# amp_lm4780.net
KiCad netlist of a schematic drawn in EAGLE
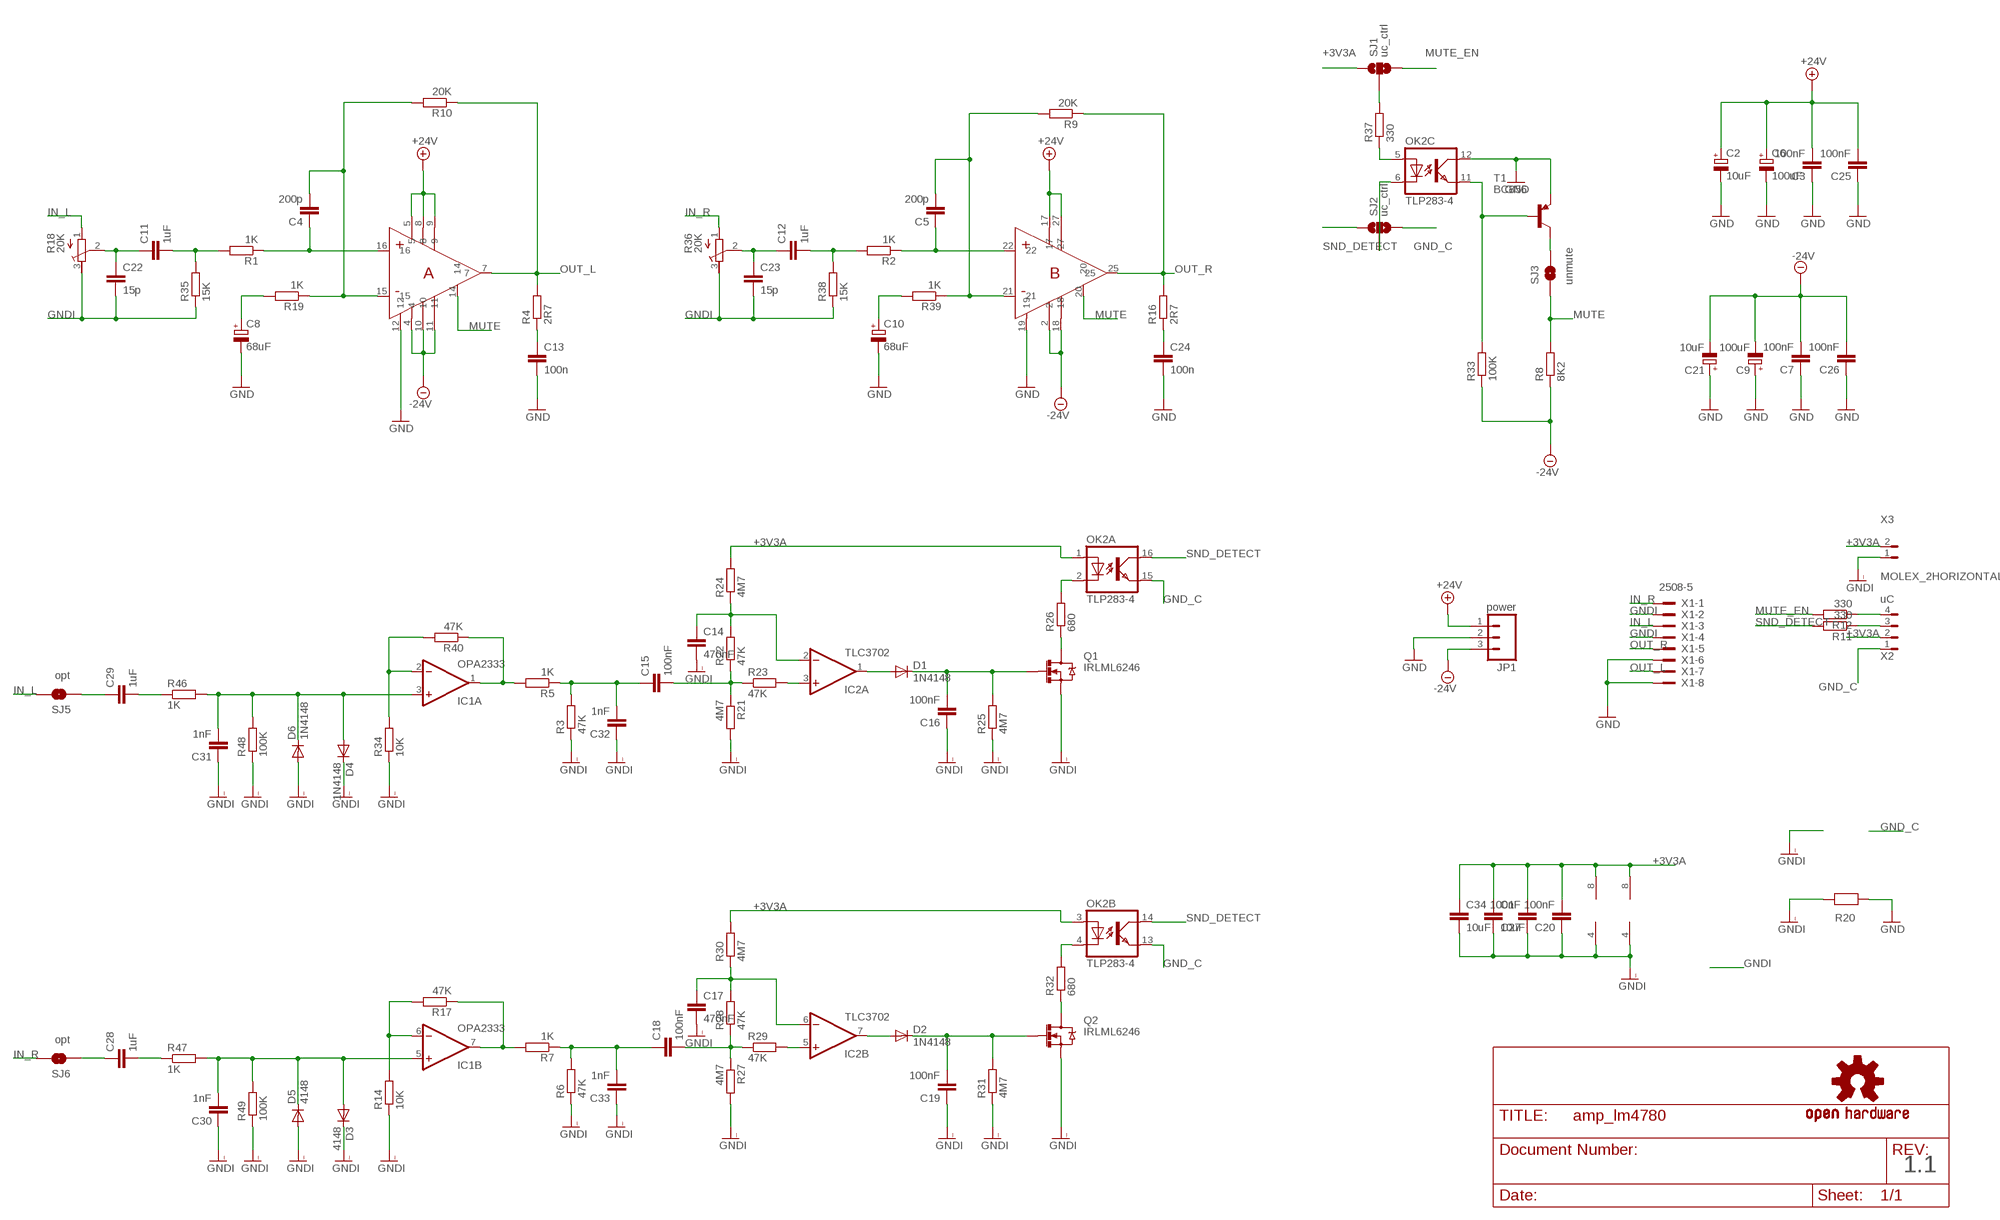
[diagram p0: schematic, sheet 1]

(export (version "E")
  (design (tool "Eeschema 10.0.6"))
  (components
    (comp (ref "C1")
      (value "10uF")
      (footprint "eagle-import:C1206K")
      (libsource (lib "eagle-import") (part "C-EUC1206K"))
    )
    (comp (ref "C2")
      (value "10uF")
      (footprint "eagle-import:PANASONIC_C")
      (libsource (lib "eagle-import") (part "CPOL-EUC"))
    )
    (comp (ref "C3")
      (value "100nF")
      (footprint "eagle-import:C0805")
      (libsource (lib "eagle-import") (part "C-EUC0805"))
    )
    (comp (ref "C4")
      (value "200p")
      (footprint "eagle-import:C0805")
      (libsource (lib "eagle-import") (part "C-EUC0805"))
    )
    (comp (ref "C5")
      (value "200p")
      (footprint "eagle-import:C0805")
      (libsource (lib "eagle-import") (part "C-EUC0805"))
    )
    (comp (ref "C6")
      (value "100uF")
      (footprint "eagle-import:PANASONIC_G")
      (libsource (lib "eagle-import") (part "CPOL-EUG"))
    )
    (comp (ref "C7")
      (value "100nF")
      (footprint "eagle-import:C0805")
      (libsource (lib "eagle-import") (part "C-EUC0805"))
    )
    (comp (ref "C8")
      (value "68uF")
      (footprint "eagle-import:PANASONIC_E")
      (libsource (lib "eagle-import") (part "CPOL-EUE"))
    )
    (comp (ref "C9")
      (value "100uF")
      (footprint "eagle-import:PANASONIC_G")
      (libsource (lib "eagle-import") (part "CPOL-EUG"))
    )
    (comp (ref "C10")
      (value "68uF")
      (footprint "eagle-import:PANASONIC_E")
      (libsource (lib "eagle-import") (part "CPOL-EUE"))
    )
    (comp (ref "C11")
      (value "1uF")
      (footprint "eagle-import:C050-035X075")
      (libsource (lib "eagle-import") (part "C-EU050-035X075"))
    )
    (comp (ref "C12")
      (value "1uF")
      (footprint "eagle-import:C050-035X075")
      (libsource (lib "eagle-import") (part "C-EU050-035X075"))
    )
    (comp (ref "C13")
      (value "100n")
      (footprint "eagle-import:C10B5")
      (libsource (lib "eagle-import") (part "C10/5"))
    )
    (comp (ref "C14")
      (value "470nF")
      (footprint "eagle-import:C0805")
      (libsource (lib "eagle-import") (part "C-EUC0805"))
    )
    (comp (ref "C15")
      (value "100nF")
      (footprint "eagle-import:C0805")
      (libsource (lib "eagle-import") (part "C-EUC0805"))
    )
    (comp (ref "C16")
      (value "100nF")
      (footprint "eagle-import:C0805")
      (libsource (lib "eagle-import") (part "C-EUC0805"))
    )
    (comp (ref "C17")
      (value "470nF")
      (footprint "eagle-import:C0805")
      (libsource (lib "eagle-import") (part "C-EUC0805"))
    )
    (comp (ref "C18")
      (value "100nF")
      (footprint "eagle-import:C0805")
      (libsource (lib "eagle-import") (part "C-EUC0805"))
    )
    (comp (ref "C19")
      (value "100nF")
      (footprint "eagle-import:C0805")
      (libsource (lib "eagle-import") (part "C-EUC0805"))
    )
    (comp (ref "C20")
      (value "100nF")
      (footprint "eagle-import:C0805")
      (libsource (lib "eagle-import") (part "C-EUC0805"))
    )
    (comp (ref "C21")
      (value "10uF")
      (footprint "eagle-import:PANASONIC_C")
      (libsource (lib "eagle-import") (part "CPOL-EUC"))
    )
    (comp (ref "C22")
      (value "15p")
      (footprint "eagle-import:C0805")
      (libsource (lib "eagle-import") (part "C-EUC0805"))
    )
    (comp (ref "C23")
      (value "15p")
      (footprint "eagle-import:C0805")
      (libsource (lib "eagle-import") (part "C-EUC0805"))
    )
    (comp (ref "C24")
      (value "100n")
      (footprint "eagle-import:C10B5")
      (libsource (lib "eagle-import") (part "C10/5"))
    )
    (comp (ref "C25")
      (value "100nF")
      (footprint "eagle-import:C0805")
      (libsource (lib "eagle-import") (part "C-EUC0805"))
    )
    (comp (ref "C26")
      (value "100nF")
      (footprint "eagle-import:C0805")
      (libsource (lib "eagle-import") (part "C-EUC0805"))
    )
    (comp (ref "C27")
      (value "100nF")
      (footprint "eagle-import:C0805")
      (libsource (lib "eagle-import") (part "C-EUC0805"))
    )
    (comp (ref "C28")
      (value "1uF")
      (footprint "eagle-import:C0805")
      (libsource (lib "eagle-import") (part "C-EUC0805"))
    )
    (comp (ref "C29")
      (value "1uF")
      (footprint "eagle-import:C0805")
      (libsource (lib "eagle-import") (part "C-EUC0805"))
    )
    (comp (ref "C30")
      (value "1nF")
      (footprint "eagle-import:C0805")
      (libsource (lib "eagle-import") (part "C-EUC0805"))
    )
    (comp (ref "C31")
      (value "1nF")
      (footprint "eagle-import:C0805")
      (libsource (lib "eagle-import") (part "C-EUC0805"))
    )
    (comp (ref "C32")
      (value "1nF")
      (footprint "eagle-import:C0805")
      (libsource (lib "eagle-import") (part "C-EUC0805"))
    )
    (comp (ref "C33")
      (value "1nF")
      (footprint "eagle-import:C0805")
      (libsource (lib "eagle-import") (part "C-EUC0805"))
    )
    (comp (ref "C34")
      (value "10uF")
      (footprint "eagle-import:C1206K")
      (libsource (lib "eagle-import") (part "C-EUC1206K"))
    )
    (comp (ref "D1")
      (value "1N4148")
      (footprint "eagle-import:SOD-123_MINI-SMA")
      (libsource (lib "eagle-import") (part "CGRM400-G1"))
    )
    (comp (ref "D2")
      (value "1N4148")
      (footprint "eagle-import:SOD-123_MINI-SMA")
      (libsource (lib "eagle-import") (part "CGRM400-G1"))
    )
    (comp (ref "D3")
      (value "4148")
      (footprint "eagle-import:SOD-123_MINI-SMA")
      (libsource (lib "eagle-import") (part "CGRM400-G1"))
    )
    (comp (ref "D4")
      (value "1N4148")
      (footprint "eagle-import:SOD-123_MINI-SMA")
      (libsource (lib "eagle-import") (part "CGRM400-G1"))
    )
    (comp (ref "D5")
      (value "4148")
      (footprint "eagle-import:SOD-123_MINI-SMA")
      (libsource (lib "eagle-import") (part "CGRM400-G1"))
    )
    (comp (ref "D6")
      (value "1N4148")
      (footprint "eagle-import:SOD-123_MINI-SMA")
      (libsource (lib "eagle-import") (part "CGRM400-G1"))
    )
    (comp (ref "IC1")
      (value "OPA2333")
      (footprint "eagle-import:SO08")
      (libsource (lib "eagle-import") (part "OPA2333D"))
    )
    (comp (ref "IC2")
      (value "TLC3702")
      (footprint "eagle-import:SO08")
      (libsource (lib "eagle-import") (part "OPA2333D"))
    )
    (comp (ref "JP1")
      (value "power")
      (footprint "eagle-import:1X03")
      (libsource (lib "eagle-import") (part "M03PTH"))
    )
    (comp (ref "OK2")
      (value "TLP283-4")
      (footprint "eagle-import:MINI-FLAT-16")
      (libsource (lib "eagle-import") (part "TLP283-4"))
    )
    (comp (ref "Q1")
      (value "IRLML6246")
      (footprint "eagle-import:SOT23-3")
      (libsource (lib "eagle-import") (part "MOSFET-NCHANNEL_SOT23-3"))
    )
    (comp (ref "Q2")
      (value "IRLML6246")
      (footprint "eagle-import:SOT23-3")
      (libsource (lib "eagle-import") (part "MOSFET-NCHANNEL_SOT23-3"))
    )
    (comp (ref "R1")
      (value "1K")
      (footprint "eagle-import:R0805W")
      (libsource (lib "eagle-import") (part "R-EU_R0805W"))
    )
    (comp (ref "R2")
      (value "1K")
      (footprint "eagle-import:R0805W")
      (libsource (lib "eagle-import") (part "R-EU_R0805W"))
    )
    (comp (ref "R3")
      (value "47K")
      (footprint "eagle-import:R0805W")
      (libsource (lib "eagle-import") (part "R-EU_R0805W"))
    )
    (comp (ref "R4")
      (value "2R7")
      (footprint "eagle-import:P0613_15")
      (libsource (lib "eagle-import") (part "R-EU_0613/15"))
    )
    (comp (ref "R5")
      (value "1K")
      (footprint "eagle-import:R0805W")
      (libsource (lib "eagle-import") (part "R-EU_R0805W"))
    )
    (comp (ref "R6")
      (value "47K")
      (footprint "eagle-import:R0805W")
      (libsource (lib "eagle-import") (part "R-EU_R0805W"))
    )
    (comp (ref "R7")
      (value "1K")
      (footprint "eagle-import:R0805W")
      (libsource (lib "eagle-import") (part "R-EU_R0805W"))
    )
    (comp (ref "R8")
      (value "8K2")
      (footprint "eagle-import:R0805W")
      (libsource (lib "eagle-import") (part "R-EU_R0805W"))
    )
    (comp (ref "R9")
      (value "20K")
      (footprint "eagle-import:R0805W")
      (libsource (lib "eagle-import") (part "R-EU_R0805W"))
    )
    (comp (ref "R10")
      (value "20K")
      (footprint "eagle-import:R0805W")
      (libsource (lib "eagle-import") (part "R-EU_R0805W"))
    )
    (comp (ref "R11")
      (value "330")
      (footprint "eagle-import:R0805W")
      (libsource (lib "eagle-import") (part "R-EU_R0805W"))
    )
    (comp (ref "R12")
      (value "330")
      (footprint "eagle-import:R0805W")
      (libsource (lib "eagle-import") (part "R-EU_R0805W"))
    )
    (comp (ref "R14")
      (value "10K")
      (footprint "eagle-import:R0805W")
      (libsource (lib "eagle-import") (part "R-EU_R0805W"))
    )
    (comp (ref "R16")
      (value "2R7")
      (footprint "eagle-import:P0613_15")
      (libsource (lib "eagle-import") (part "R-EU_0613/15"))
    )
    (comp (ref "R17")
      (value "47K")
      (footprint "eagle-import:R0805W")
      (libsource (lib "eagle-import") (part "R-EU_R0805W"))
    )
    (comp (ref "R18")
      (value "20K")
      (footprint "eagle-import:RTRIM3339P")
      (libsource (lib "eagle-import") (part "R-TRIMM3339P"))
    )
    (comp (ref "R19")
      (value "1K")
      (footprint "eagle-import:P0613_15")
      (libsource (lib "eagle-import") (part "R-EU_0613/15"))
    )
    (comp (ref "R20")
      (value "0R_0805")
      (footprint "eagle-import:R0805W")
      (libsource (lib "eagle-import") (part "0R_0805"))
    )
    (comp (ref "R21")
      (value "4M7")
      (footprint "eagle-import:R0805W")
      (libsource (lib "eagle-import") (part "R-EU_R0805W"))
    )
    (comp (ref "R22")
      (value "47K")
      (footprint "eagle-import:R0805W")
      (libsource (lib "eagle-import") (part "R-EU_R0805W"))
    )
    (comp (ref "R23")
      (value "47K")
      (footprint "eagle-import:R0805W")
      (libsource (lib "eagle-import") (part "R-EU_R0805W"))
    )
    (comp (ref "R24")
      (value "4M7")
      (footprint "eagle-import:R0805W")
      (libsource (lib "eagle-import") (part "R-EU_R0805W"))
    )
    (comp (ref "R25")
      (value "4M7")
      (footprint "eagle-import:R0805W")
      (libsource (lib "eagle-import") (part "R-EU_R0805W"))
    )
    (comp (ref "R26")
      (value "680")
      (footprint "eagle-import:R0805W")
      (libsource (lib "eagle-import") (part "R-EU_R0805W"))
    )
    (comp (ref "R27")
      (value "4M7")
      (footprint "eagle-import:R0805W")
      (libsource (lib "eagle-import") (part "R-EU_R0805W"))
    )
    (comp (ref "R28")
      (value "47K")
      (footprint "eagle-import:R0805W")
      (libsource (lib "eagle-import") (part "R-EU_R0805W"))
    )
    (comp (ref "R29")
      (value "47K")
      (footprint "eagle-import:R0805W")
      (libsource (lib "eagle-import") (part "R-EU_R0805W"))
    )
    (comp (ref "R30")
      (value "4M7")
      (footprint "eagle-import:R0805W")
      (libsource (lib "eagle-import") (part "R-EU_R0805W"))
    )
    (comp (ref "R31")
      (value "4M7")
      (footprint "eagle-import:R0805W")
      (libsource (lib "eagle-import") (part "R-EU_R0805W"))
    )
    (comp (ref "R32")
      (value "680")
      (footprint "eagle-import:R0805W")
      (libsource (lib "eagle-import") (part "R-EU_R0805W"))
    )
    (comp (ref "R33")
      (value "100K")
      (footprint "eagle-import:R0805W")
      (libsource (lib "eagle-import") (part "R-EU_R0805W"))
    )
    (comp (ref "R34")
      (value "10K")
      (footprint "eagle-import:R0805W")
      (libsource (lib "eagle-import") (part "R-EU_R0805W"))
    )
    (comp (ref "R35")
      (value "15K")
      (footprint "eagle-import:R0805W")
      (libsource (lib "eagle-import") (part "R-EU_R0805W"))
    )
    (comp (ref "R36")
      (value "20K")
      (footprint "eagle-import:RTRIM3339P")
      (libsource (lib "eagle-import") (part "R-TRIMM3339P"))
    )
    (comp (ref "R37")
      (value "330")
      (footprint "eagle-import:R0805W")
      (libsource (lib "eagle-import") (part "R-EU_R0805W"))
    )
    (comp (ref "R38")
      (value "15K")
      (footprint "eagle-import:R0805W")
      (libsource (lib "eagle-import") (part "R-EU_R0805W"))
    )
    (comp (ref "R39")
      (value "1K")
      (footprint "eagle-import:P0613_15")
      (libsource (lib "eagle-import") (part "R-EU_0613/15"))
    )
    (comp (ref "R40")
      (value "47K")
      (footprint "eagle-import:R0805W")
      (libsource (lib "eagle-import") (part "R-EU_R0805W"))
    )
    (comp (ref "R46")
      (value "1K")
      (footprint "eagle-import:R0805W")
      (libsource (lib "eagle-import") (part "R-EU_R0805W"))
    )
    (comp (ref "R47")
      (value "1K")
      (footprint "eagle-import:R0805W")
      (libsource (lib "eagle-import") (part "R-EU_R0805W"))
    )
    (comp (ref "R48")
      (value "100K")
      (footprint "eagle-import:R0805W")
      (libsource (lib "eagle-import") (part "R-EU_R0805W"))
    )
    (comp (ref "R49")
      (value "100K")
      (footprint "eagle-import:R0805W")
      (libsource (lib "eagle-import") (part "R-EU_R0805W"))
    )
    (comp (ref "SJ1")
      (value "uc_ctrl")
      (footprint "eagle-import:SJ_3_PASTE2&3")
      (libsource (lib "eagle-import") (part "SOLDERJUMPER_2WAYPASTE2&3"))
    )
    (comp (ref "SJ2")
      (value "uc_ctrl")
      (footprint "eagle-import:SJ_3_PASTE2&3")
      (libsource (lib "eagle-import") (part "SOLDERJUMPER_2WAYPASTE2&3"))
    )
    (comp (ref "SJ3")
      (value "unmute")
      (footprint "eagle-import:SJ_2S-TRACE")
      (libsource (lib "eagle-import") (part "SOLDERJUMPERTRACE"))
    )
    (comp (ref "SJ5")
      (value "opt")
      (footprint "eagle-import:SJ_2S-TRACE")
      (libsource (lib "eagle-import") (part "SOLDERJUMPERTRACE"))
    )
    (comp (ref "SJ6")
      (value "opt")
      (footprint "eagle-import:SJ_2S-TRACE")
      (libsource (lib "eagle-import") (part "SOLDERJUMPERTRACE"))
    )
    (comp (ref "T1")
      (value "BC856")
      (footprint "eagle-import:SOT23-BEC")
      (libsource (lib "eagle-import") (part "-PNP-SOT23-BECBC856A"))
    )
    (comp (ref "U$1")
      (value "LM4780_H")
      (footprint "eagle-import:TO220-27_HOR")
      (libsource (lib "eagle-import") (part "LM4780_H"))
    )
    (comp (ref "U$7")
      (value "OSHW-LOGOM")
      (footprint "eagle-import:OSHW-LOGO-M")
      (libsource (lib "eagle-import") (part "OSHW-LOGOM"))
    )
    (comp (ref "X1")
      (value "2508-5")
      (footprint "eagle-import:PAK100_2500-5-08")
      (libsource (lib "eagle-import") (part "2508-5"))
    )
    (comp (ref "X2")
      (value "uC")
      (footprint "eagle-import:0530480401")
      (libsource (lib "eagle-import") (part "MOLEX_4HORIZONTAL"))
    )
    (comp (ref "X3")
      (value "MOLEX_2HORIZONTAL")
      (footprint "eagle-import:0530480210")
      (libsource (lib "eagle-import") (part "MOLEX_2HORIZONTAL"))
    )
  )
  (nets
    (net (code "1") (name "+24V") (class "Default")
      (node (ref "C2") (pin "+") (pinfunction "+_+") (pintype "passive"))
      (node (ref "C25") (pin "2") (pinfunction "2_2") (pintype "passive"))
      (node (ref "C3") (pin "2") (pinfunction "2_2") (pintype "passive"))
      (node (ref "C6") (pin "+") (pinfunction "+_+") (pintype "passive"))
      (node (ref "JP1") (pin "1") (pinfunction "1_1") (pintype "passive"))
      (node (ref "U$1") (pin "17") (pinfunction "17_17") (pintype "power_in"))
      (node (ref "U$1") (pin "27") (pinfunction "27_27") (pintype "power_in"))
      (node (ref "U$1") (pin "5") (pinfunction "5_5") (pintype "power_in"))
      (node (ref "U$1") (pin "8") (pinfunction "8_8") (pintype "power_in"))
      (node (ref "U$1") (pin "9") (pinfunction "9_9") (pintype "power_in"))
    )
    (net (code "2") (name "-24V") (class "Default")
      (node (ref "C21") (pin "-") (pinfunction "-_-") (pintype "passive"))
      (node (ref "C26") (pin "2") (pinfunction "2_2") (pintype "passive"))
      (node (ref "C7") (pin "2") (pinfunction "2_2") (pintype "passive"))
      (node (ref "C9") (pin "-") (pinfunction "-_-") (pintype "passive"))
      (node (ref "JP1") (pin "3") (pinfunction "3_3") (pintype "passive"))
      (node (ref "R33") (pin "1") (pinfunction "1_1") (pintype "passive"))
      (node (ref "R8") (pin "1") (pinfunction "1_1") (pintype "passive"))
      (node (ref "U$1") (pin "10") (pinfunction "10_10") (pintype "power_in"))
      (node (ref "U$1") (pin "11") (pinfunction "11_11") (pintype "power_in"))
      (node (ref "U$1") (pin "18") (pinfunction "18_18") (pintype "power_in"))
      (node (ref "U$1") (pin "2") (pinfunction "2_2") (pintype "power_in"))
      (node (ref "U$1") (pin "4") (pinfunction "4_4") (pintype "power_in"))
    )
    (net (code "3") (name "/+3V3A") (class "Default")
      (node (ref "C1") (pin "1") (pinfunction "1_1") (pintype "passive"))
      (node (ref "C20") (pin "2") (pinfunction "2_2") (pintype "passive"))
      (node (ref "C27") (pin "2") (pinfunction "2_2") (pintype "passive"))
      (node (ref "C34") (pin "1") (pinfunction "1_1") (pintype "passive"))
      (node (ref "IC1") (pin "8") (pinfunction "V+_8") (pintype "power_in"))
      (node (ref "IC2") (pin "8") (pinfunction "V+_8") (pintype "power_in"))
      (node (ref "OK2") (pin "1") (pinfunction "A_1") (pintype "passive"))
      (node (ref "OK2") (pin "3") (pinfunction "A_3") (pintype "passive"))
      (node (ref "R24") (pin "2") (pinfunction "2_2") (pintype "passive"))
      (node (ref "R30") (pin "2") (pinfunction "2_2") (pintype "passive"))
      (node (ref "SJ1") (pin "1") (pinfunction "1_1") (pintype "passive"))
      (node (ref "X2") (pin "2") (pinfunction "3_2") (pintype "passive"))
      (node (ref "X3") (pin "2") (pinfunction "1_2") (pintype "passive"))
    )
    (net (code "4") (name "/GND_C") (class "Default")
      (node (ref "OK2") (pin "13") (pinfunction "EMIT_13") (pintype "passive"))
      (node (ref "OK2") (pin "15") (pinfunction "EMIT_15") (pintype "passive"))
      (node (ref "SJ2") (pin "3") (pinfunction "3_3") (pintype "passive"))
      (node (ref "X2") (pin "1") (pinfunction "4_1") (pintype "passive"))
    )
    (net (code "5") (name "/IN_L") (class "Default")
      (node (ref "R18") (pin "1") (pinfunction "A_1") (pintype "passive"))
      (node (ref "SJ5") (pin "2") (pinfunction "2_2") (pintype "passive"))
      (node (ref "X1") (pin "3") (pinfunction "KL_3") (pintype "passive"))
    )
    (net (code "6") (name "/IN_R") (class "Default")
      (node (ref "R36") (pin "1") (pinfunction "A_1") (pintype "passive"))
      (node (ref "SJ6") (pin "2") (pinfunction "2_2") (pintype "passive"))
      (node (ref "X1") (pin "1") (pinfunction "KL_1") (pintype "passive"))
    )
    (net (code "7") (name "/MUTE") (class "Default")
      (node (ref "R8") (pin "2") (pinfunction "2_2") (pintype "passive"))
      (node (ref "SJ3") (pin "1") (pinfunction "1_1") (pintype "passive"))
      (node (ref "U$1") (pin "14") (pinfunction "14_14") (pintype "bidirectional"))
      (node (ref "U$1") (pin "20") (pinfunction "20_20") (pintype "bidirectional"))
    )
    (net (code "8") (name "/MUTE_EN") (class "Default")
      (node (ref "R12") (pin "2") (pinfunction "2_2") (pintype "passive"))
      (node (ref "SJ1") (pin "3") (pinfunction "3_3") (pintype "passive"))
    )
    (net (code "9") (name "/OUT_L") (class "Default")
      (node (ref "R10") (pin "1") (pinfunction "1_1") (pintype "passive"))
      (node (ref "R4") (pin "2") (pinfunction "2_2") (pintype "passive"))
      (node (ref "U$1") (pin "7") (pinfunction "7_7") (pintype "output"))
      (node (ref "X1") (pin "7") (pinfunction "KL_7") (pintype "passive"))
    )
    (net (code "10") (name "/OUT_R") (class "Default")
      (node (ref "R16") (pin "2") (pinfunction "2_2") (pintype "passive"))
      (node (ref "R9") (pin "1") (pinfunction "1_1") (pintype "passive"))
      (node (ref "U$1") (pin "25") (pinfunction "25_25") (pintype "output"))
      (node (ref "X1") (pin "5") (pinfunction "KL_5") (pintype "passive"))
    )
    (net (code "11") (name "/SND_DETECT") (class "Default")
      (node (ref "OK2") (pin "14") (pinfunction "COL_14") (pintype "passive"))
      (node (ref "OK2") (pin "16") (pinfunction "COL_16") (pintype "passive"))
      (node (ref "R11") (pin "2") (pinfunction "2_2") (pintype "passive"))
      (node (ref "SJ2") (pin "1") (pinfunction "1_1") (pintype "passive"))
    )
    (net (code "12") (name "GND") (class "Default")
      (node (ref "C10") (pin "-") (pinfunction "-_-") (pintype "passive"))
      (node (ref "C13") (pin "2") (pinfunction "2_2") (pintype "passive"))
      (node (ref "C2") (pin "-") (pinfunction "-_-") (pintype "passive"))
      (node (ref "C21") (pin "+") (pinfunction "+_+") (pintype "passive"))
      (node (ref "C24") (pin "2") (pinfunction "2_2") (pintype "passive"))
      (node (ref "C25") (pin "1") (pinfunction "1_1") (pintype "passive"))
      (node (ref "C26") (pin "1") (pinfunction "1_1") (pintype "passive"))
      (node (ref "C3") (pin "1") (pinfunction "1_1") (pintype "passive"))
      (node (ref "C6") (pin "-") (pinfunction "-_-") (pintype "passive"))
      (node (ref "C7") (pin "1") (pinfunction "1_1") (pintype "passive"))
      (node (ref "C8") (pin "-") (pinfunction "-_-") (pintype "passive"))
      (node (ref "C9") (pin "+") (pinfunction "+_+") (pintype "passive"))
      (node (ref "JP1") (pin "2") (pinfunction "2_2") (pintype "passive"))
      (node (ref "OK2") (pin "12") (pinfunction "COL_12") (pintype "passive"))
      (node (ref "R20") (pin "2") (pinfunction "P$2_2") (pintype "bidirectional"))
      (node (ref "T1") (pin "E") (pinfunction "E_E") (pintype "passive"))
      (node (ref "U$1") (pin "12") (pinfunction "12_12") (pintype "power_in"))
      (node (ref "U$1") (pin "19") (pinfunction "19_19") (pintype "power_in"))
      (node (ref "X1") (pin "6") (pinfunction "KL_6") (pintype "passive"))
      (node (ref "X1") (pin "8") (pinfunction "KL_8") (pintype "passive"))
    )
    (net (code "13") (name "GNDI") (class "Default")
      (node (ref "C1") (pin "2") (pinfunction "2_2") (pintype "passive"))
      (node (ref "C14") (pin "2") (pinfunction "2_2") (pintype "passive"))
      (node (ref "C16") (pin "1") (pinfunction "1_1") (pintype "passive"))
      (node (ref "C17") (pin "2") (pinfunction "2_2") (pintype "passive"))
      (node (ref "C19") (pin "1") (pinfunction "1_1") (pintype "passive"))
      (node (ref "C20") (pin "1") (pinfunction "1_1") (pintype "passive"))
      (node (ref "C22") (pin "2") (pinfunction "2_2") (pintype "passive"))
      (node (ref "C23") (pin "2") (pinfunction "2_2") (pintype "passive"))
      (node (ref "C27") (pin "1") (pinfunction "1_1") (pintype "passive"))
      (node (ref "C30") (pin "1") (pinfunction "1_1") (pintype "passive"))
      (node (ref "C31") (pin "1") (pinfunction "1_1") (pintype "passive"))
      (node (ref "C32") (pin "1") (pinfunction "1_1") (pintype "passive"))
      (node (ref "C33") (pin "1") (pinfunction "1_1") (pintype "passive"))
      (node (ref "C34") (pin "2") (pinfunction "2_2") (pintype "passive"))
      (node (ref "D3") (pin "C") (pinfunction "C_C") (pintype "passive"))
      (node (ref "D4") (pin "C") (pinfunction "C_C") (pintype "passive"))
      (node (ref "D5") (pin "A") (pinfunction "A_A") (pintype "passive"))
      (node (ref "D6") (pin "A") (pinfunction "A_A") (pintype "passive"))
      (node (ref "IC1") (pin "4") (pinfunction "V-_4") (pintype "power_in"))
      (node (ref "IC2") (pin "4") (pinfunction "V-_4") (pintype "power_in"))
      (node (ref "Q1") (pin "2") (pinfunction "S_2") (pintype "passive"))
      (node (ref "Q2") (pin "2") (pinfunction "S_2") (pintype "passive"))
      (node (ref "R14") (pin "1") (pinfunction "1_1") (pintype "passive"))
      (node (ref "R18") (pin "3") (pinfunction "E_3") (pintype "passive"))
      (node (ref "R20") (pin "1") (pinfunction "P$1_1") (pintype "bidirectional"))
      (node (ref "R21") (pin "2") (pinfunction "2_2") (pintype "passive"))
      (node (ref "R25") (pin "1") (pinfunction "1_1") (pintype "passive"))
      (node (ref "R27") (pin "2") (pinfunction "2_2") (pintype "passive"))
      (node (ref "R3") (pin "1") (pinfunction "1_1") (pintype "passive"))
      (node (ref "R31") (pin "1") (pinfunction "1_1") (pintype "passive"))
      (node (ref "R34") (pin "1") (pinfunction "1_1") (pintype "passive"))
      (node (ref "R35") (pin "1") (pinfunction "1_1") (pintype "passive"))
      (node (ref "R36") (pin "3") (pinfunction "E_3") (pintype "passive"))
      (node (ref "R38") (pin "1") (pinfunction "1_1") (pintype "passive"))
      (node (ref "R48") (pin "1") (pinfunction "1_1") (pintype "passive"))
      (node (ref "R49") (pin "1") (pinfunction "1_1") (pintype "passive"))
      (node (ref "R6") (pin "1") (pinfunction "1_1") (pintype "passive"))
      (node (ref "X1") (pin "2") (pinfunction "KL_2") (pintype "passive"))
      (node (ref "X1") (pin "4") (pinfunction "KL_4") (pintype "passive"))
      (node (ref "X3") (pin "1") (pinfunction "2_1") (pintype "passive"))
    )
    (net (code "14") (name "Net-(C4-Pad1)") (class "Default")
      (node (ref "C4") (pin "1") (pinfunction "1_1") (pintype "passive"))
      (node (ref "R1") (pin "1") (pinfunction "1_1") (pintype "passive"))
      (node (ref "U$1") (pin "16") (pinfunction "16_16") (pintype "input"))
    )
    (net (code "15") (name "Net-(C4-Pad2)") (class "Default")
      (node (ref "C4") (pin "2") (pinfunction "2_2") (pintype "passive"))
      (node (ref "R10") (pin "2") (pinfunction "2_2") (pintype "passive"))
      (node (ref "R19") (pin "1") (pinfunction "1_1") (pintype "passive"))
      (node (ref "U$1") (pin "15") (pinfunction "15_15") (pintype "input"))
    )
    (net (code "16") (name "Net-(C5-Pad1)") (class "Default")
      (node (ref "C5") (pin "1") (pinfunction "1_1") (pintype "passive"))
      (node (ref "R2") (pin "1") (pinfunction "1_1") (pintype "passive"))
      (node (ref "U$1") (pin "22") (pinfunction "22_22") (pintype "input"))
    )
    (net (code "17") (name "Net-(C5-Pad2)") (class "Default")
      (node (ref "C5") (pin "2") (pinfunction "2_2") (pintype "passive"))
      (node (ref "R39") (pin "1") (pinfunction "1_1") (pintype "passive"))
      (node (ref "R9") (pin "2") (pinfunction "2_2") (pintype "passive"))
      (node (ref "U$1") (pin "21") (pinfunction "21_21") (pintype "input"))
    )
    (net (code "18") (name "Net-(C8-Pad+)") (class "Default")
      (node (ref "C8") (pin "+") (pinfunction "+_+") (pintype "passive"))
      (node (ref "R19") (pin "2") (pinfunction "2_2") (pintype "passive"))
    )
    (net (code "19") (name "Net-(C10-Pad+)") (class "Default")
      (node (ref "C10") (pin "+") (pinfunction "+_+") (pintype "passive"))
      (node (ref "R39") (pin "2") (pinfunction "2_2") (pintype "passive"))
    )
    (net (code "20") (name "Net-(C11-Pad2)") (class "Default")
      (node (ref "C11") (pin "2") (pinfunction "2_2") (pintype "passive"))
      (node (ref "R1") (pin "2") (pinfunction "2_2") (pintype "passive"))
      (node (ref "R35") (pin "2") (pinfunction "2_2") (pintype "passive"))
    )
    (net (code "21") (name "Net-(C12-Pad2)") (class "Default")
      (node (ref "C12") (pin "2") (pinfunction "2_2") (pintype "passive"))
      (node (ref "R2") (pin "2") (pinfunction "2_2") (pintype "passive"))
      (node (ref "R38") (pin "2") (pinfunction "2_2") (pintype "passive"))
    )
    (net (code "22") (name "Net-(C13-Pad1)") (class "Default")
      (node (ref "C13") (pin "1") (pinfunction "1_1") (pintype "passive"))
      (node (ref "R4") (pin "1") (pinfunction "1_1") (pintype "passive"))
    )
    (net (code "23") (name "Net-(C15-Pad1)") (class "Default")
      (node (ref "C15") (pin "1") (pinfunction "1_1") (pintype "passive"))
      (node (ref "C32") (pin "2") (pinfunction "2_2") (pintype "passive"))
      (node (ref "R3") (pin "2") (pinfunction "2_2") (pintype "passive"))
      (node (ref "R5") (pin "1") (pinfunction "1_1") (pintype "passive"))
    )
    (net (code "24") (name "Net-(C15-Pad2)") (class "Default")
      (node (ref "C15") (pin "2") (pinfunction "2_2") (pintype "passive"))
      (node (ref "R21") (pin "1") (pinfunction "1_1") (pintype "passive"))
      (node (ref "R22") (pin "1") (pinfunction "1_1") (pintype "passive"))
      (node (ref "R23") (pin "1") (pinfunction "1_1") (pintype "passive"))
    )
    (net (code "25") (name "Net-(C18-Pad1)") (class "Default")
      (node (ref "C18") (pin "1") (pinfunction "1_1") (pintype "passive"))
      (node (ref "C33") (pin "2") (pinfunction "2_2") (pintype "passive"))
      (node (ref "R6") (pin "2") (pinfunction "2_2") (pintype "passive"))
      (node (ref "R7") (pin "1") (pinfunction "1_1") (pintype "passive"))
    )
    (net (code "26") (name "Net-(C18-Pad2)") (class "Default")
      (node (ref "C18") (pin "2") (pinfunction "2_2") (pintype "passive"))
      (node (ref "R27") (pin "1") (pinfunction "1_1") (pintype "passive"))
      (node (ref "R28") (pin "1") (pinfunction "1_1") (pintype "passive"))
      (node (ref "R29") (pin "1") (pinfunction "1_1") (pintype "passive"))
    )
    (net (code "27") (name "Net-(C24-Pad1)") (class "Default")
      (node (ref "C24") (pin "1") (pinfunction "1_1") (pintype "passive"))
      (node (ref "R16") (pin "1") (pinfunction "1_1") (pintype "passive"))
    )
    (net (code "28") (name "Net-(C28-Pad1)") (class "Default")
      (node (ref "C28") (pin "1") (pinfunction "1_1") (pintype "passive"))
      (node (ref "SJ6") (pin "1") (pinfunction "1_1") (pintype "passive"))
    )
    (net (code "29") (name "Net-(C28-Pad2)") (class "Default")
      (node (ref "C28") (pin "2") (pinfunction "2_2") (pintype "passive"))
      (node (ref "R47") (pin "1") (pinfunction "1_1") (pintype "passive"))
    )
    (net (code "30") (name "Net-(C29-Pad1)") (class "Default")
      (node (ref "C29") (pin "1") (pinfunction "1_1") (pintype "passive"))
      (node (ref "SJ5") (pin "1") (pinfunction "1_1") (pintype "passive"))
    )
    (net (code "31") (name "Net-(C29-Pad2)") (class "Default")
      (node (ref "C29") (pin "2") (pinfunction "2_2") (pintype "passive"))
      (node (ref "R46") (pin "1") (pinfunction "1_1") (pintype "passive"))
    )
    (net (code "32") (name "Net-(IC1A-+IN)") (class "Default")
      (node (ref "C31") (pin "2") (pinfunction "2_2") (pintype "passive"))
      (node (ref "D4") (pin "A") (pinfunction "A_A") (pintype "passive"))
      (node (ref "D6") (pin "C") (pinfunction "C_C") (pintype "passive"))
      (node (ref "IC1") (pin "3") (pinfunction "+IN_3") (pintype "input"))
      (node (ref "R46") (pin "2") (pinfunction "2_2") (pintype "passive"))
      (node (ref "R48") (pin "2") (pinfunction "2_2") (pintype "passive"))
    )
    (net (code "33") (name "Net-(IC1A--IN)") (class "Default")
      (node (ref "IC1") (pin "2") (pinfunction "-IN_2") (pintype "input"))
      (node (ref "R34") (pin "2") (pinfunction "2_2") (pintype "passive"))
      (node (ref "R40") (pin "2") (pinfunction "2_2") (pintype "passive"))
    )
    (net (code "34") (name "Net-(IC1A-OUT)") (class "Default")
      (node (ref "IC1") (pin "1") (pinfunction "OUT_1") (pintype "output"))
      (node (ref "R40") (pin "1") (pinfunction "1_1") (pintype "passive"))
      (node (ref "R5") (pin "2") (pinfunction "2_2") (pintype "passive"))
    )
    (net (code "35") (name "Net-(IC1B-+IN)") (class "Default")
      (node (ref "C30") (pin "2") (pinfunction "2_2") (pintype "passive"))
      (node (ref "D3") (pin "A") (pinfunction "A_A") (pintype "passive"))
      (node (ref "D5") (pin "C") (pinfunction "C_C") (pintype "passive"))
      (node (ref "IC1") (pin "5") (pinfunction "+IN_5") (pintype "input"))
      (node (ref "R47") (pin "2") (pinfunction "2_2") (pintype "passive"))
      (node (ref "R49") (pin "2") (pinfunction "2_2") (pintype "passive"))
    )
    (net (code "36") (name "Net-(IC1B--IN)") (class "Default")
      (node (ref "IC1") (pin "6") (pinfunction "-IN_6") (pintype "input"))
      (node (ref "R14") (pin "2") (pinfunction "2_2") (pintype "passive"))
      (node (ref "R17") (pin "2") (pinfunction "2_2") (pintype "passive"))
    )
    (net (code "37") (name "Net-(IC1B-OUT)") (class "Default")
      (node (ref "IC1") (pin "7") (pinfunction "OUT_7") (pintype "output"))
      (node (ref "R17") (pin "1") (pinfunction "1_1") (pintype "passive"))
      (node (ref "R7") (pin "2") (pinfunction "2_2") (pintype "passive"))
    )
    (net (code "38") (name "Net-(IC2A-+IN)") (class "Default")
      (node (ref "IC2") (pin "3") (pinfunction "+IN_3") (pintype "input"))
      (node (ref "R23") (pin "2") (pinfunction "2_2") (pintype "passive"))
    )
    (net (code "39") (name "Net-(IC2A--IN)") (class "Default")
      (node (ref "C14") (pin "1") (pinfunction "1_1") (pintype "passive"))
      (node (ref "IC2") (pin "2") (pinfunction "-IN_2") (pintype "input"))
      (node (ref "R22") (pin "2") (pinfunction "2_2") (pintype "passive"))
      (node (ref "R24") (pin "1") (pinfunction "1_1") (pintype "passive"))
    )
    (net (code "40") (name "Net-(IC2A-OUT)") (class "Default")
      (node (ref "D1") (pin "A") (pinfunction "A_A") (pintype "passive"))
      (node (ref "IC2") (pin "1") (pinfunction "OUT_1") (pintype "output"))
    )
    (net (code "41") (name "Net-(IC2B-+IN)") (class "Default")
      (node (ref "IC2") (pin "5") (pinfunction "+IN_5") (pintype "input"))
      (node (ref "R29") (pin "2") (pinfunction "2_2") (pintype "passive"))
    )
    (net (code "42") (name "Net-(IC2B--IN)") (class "Default")
      (node (ref "C17") (pin "1") (pinfunction "1_1") (pintype "passive"))
      (node (ref "IC2") (pin "6") (pinfunction "-IN_6") (pintype "input"))
      (node (ref "R28") (pin "2") (pinfunction "2_2") (pintype "passive"))
      (node (ref "R30") (pin "1") (pinfunction "1_1") (pintype "passive"))
    )
    (net (code "43") (name "Net-(IC2B-OUT)") (class "Default")
      (node (ref "D2") (pin "A") (pinfunction "A_A") (pintype "passive"))
      (node (ref "IC2") (pin "7") (pinfunction "OUT_7") (pintype "output"))
    )
    (net (code "44") (name "Net-(OK2A-C)") (class "Default")
      (node (ref "OK2") (pin "2") (pinfunction "C_2") (pintype "passive"))
      (node (ref "R26") (pin "2") (pinfunction "2_2") (pintype "passive"))
    )
    (net (code "45") (name "Net-(OK2B-C)") (class "Default")
      (node (ref "OK2") (pin "4") (pinfunction "C_4") (pintype "passive"))
      (node (ref "R32") (pin "2") (pinfunction "2_2") (pintype "passive"))
    )
    (net (code "46") (name "Net-(OK2C-A)") (class "Default")
      (node (ref "OK2") (pin "5") (pinfunction "A_5") (pintype "passive"))
      (node (ref "R37") (pin "1") (pinfunction "1_1") (pintype "passive"))
    )
    (net (code "47") (name "Net-(OK2C-C)") (class "Default")
      (node (ref "OK2") (pin "6") (pinfunction "C_6") (pintype "passive"))
      (node (ref "SJ2") (pin "2") (pinfunction "2_2") (pintype "passive"))
    )
    (net (code "48") (name "Net-(OK2C-EMIT)") (class "Default")
      (node (ref "OK2") (pin "11") (pinfunction "EMIT_11") (pintype "passive"))
      (node (ref "R33") (pin "2") (pinfunction "2_2") (pintype "passive"))
      (node (ref "T1") (pin "B") (pinfunction "B_B") (pintype "passive"))
    )
    (net (code "49") (name "Net-(Q1-D)") (class "Default")
      (node (ref "Q1") (pin "3") (pinfunction "D_3") (pintype "passive"))
      (node (ref "R26") (pin "1") (pinfunction "1_1") (pintype "passive"))
    )
    (net (code "50") (name "Net-(Q1-G)") (class "Default")
      (node (ref "C16") (pin "2") (pinfunction "2_2") (pintype "passive"))
      (node (ref "D1") (pin "C") (pinfunction "C_C") (pintype "passive"))
      (node (ref "Q1") (pin "1") (pinfunction "G_1") (pintype "passive"))
      (node (ref "R25") (pin "2") (pinfunction "2_2") (pintype "passive"))
    )
    (net (code "51") (name "Net-(Q2-D)") (class "Default")
      (node (ref "Q2") (pin "3") (pinfunction "D_3") (pintype "passive"))
      (node (ref "R32") (pin "1") (pinfunction "1_1") (pintype "passive"))
    )
    (net (code "52") (name "Net-(Q2-G)") (class "Default")
      (node (ref "C19") (pin "2") (pinfunction "2_2") (pintype "passive"))
      (node (ref "D2") (pin "C") (pinfunction "C_C") (pintype "passive"))
      (node (ref "Q2") (pin "1") (pinfunction "G_1") (pintype "passive"))
      (node (ref "R31") (pin "2") (pinfunction "2_2") (pintype "passive"))
    )
    (net (code "53") (name "Net-(R18-S)") (class "Default")
      (node (ref "C11") (pin "1") (pinfunction "1_1") (pintype "passive"))
      (node (ref "C22") (pin "1") (pinfunction "1_1") (pintype "passive"))
      (node (ref "R18") (pin "2") (pinfunction "S_2") (pintype "passive"))
    )
    (net (code "54") (name "Net-(R36-S)") (class "Default")
      (node (ref "C12") (pin "1") (pinfunction "1_1") (pintype "passive"))
      (node (ref "C23") (pin "1") (pinfunction "1_1") (pintype "passive"))
      (node (ref "R36") (pin "2") (pinfunction "S_2") (pintype "passive"))
    )
    (net (code "55") (name "Net-(R37-Pad2)") (class "Default")
      (node (ref "R37") (pin "2") (pinfunction "2_2") (pintype "passive"))
      (node (ref "SJ1") (pin "2") (pinfunction "2_2") (pintype "passive"))
    )
    (net (code "56") (name "Net-(SJ3-Pad2)") (class "Default")
      (node (ref "SJ3") (pin "2") (pinfunction "2_2") (pintype "passive"))
      (node (ref "T1") (pin "C") (pinfunction "C_C") (pintype "passive"))
    )
    (net (code "57") (name "Net-(X2-1)") (class "Default")
      (node (ref "R12") (pin "1") (pinfunction "1_1") (pintype "passive"))
      (node (ref "X2") (pin "4") (pinfunction "1_4") (pintype "passive"))
    )
    (net (code "58") (name "Net-(X2-2)") (class "Default")
      (node (ref "R11") (pin "1") (pinfunction "1_1") (pintype "passive"))
      (node (ref "X2") (pin "3") (pinfunction "2_3") (pintype "passive"))
    )
  )
)
